# netzteil.net
KiCad netlist of a schematic drawn in EAGLE
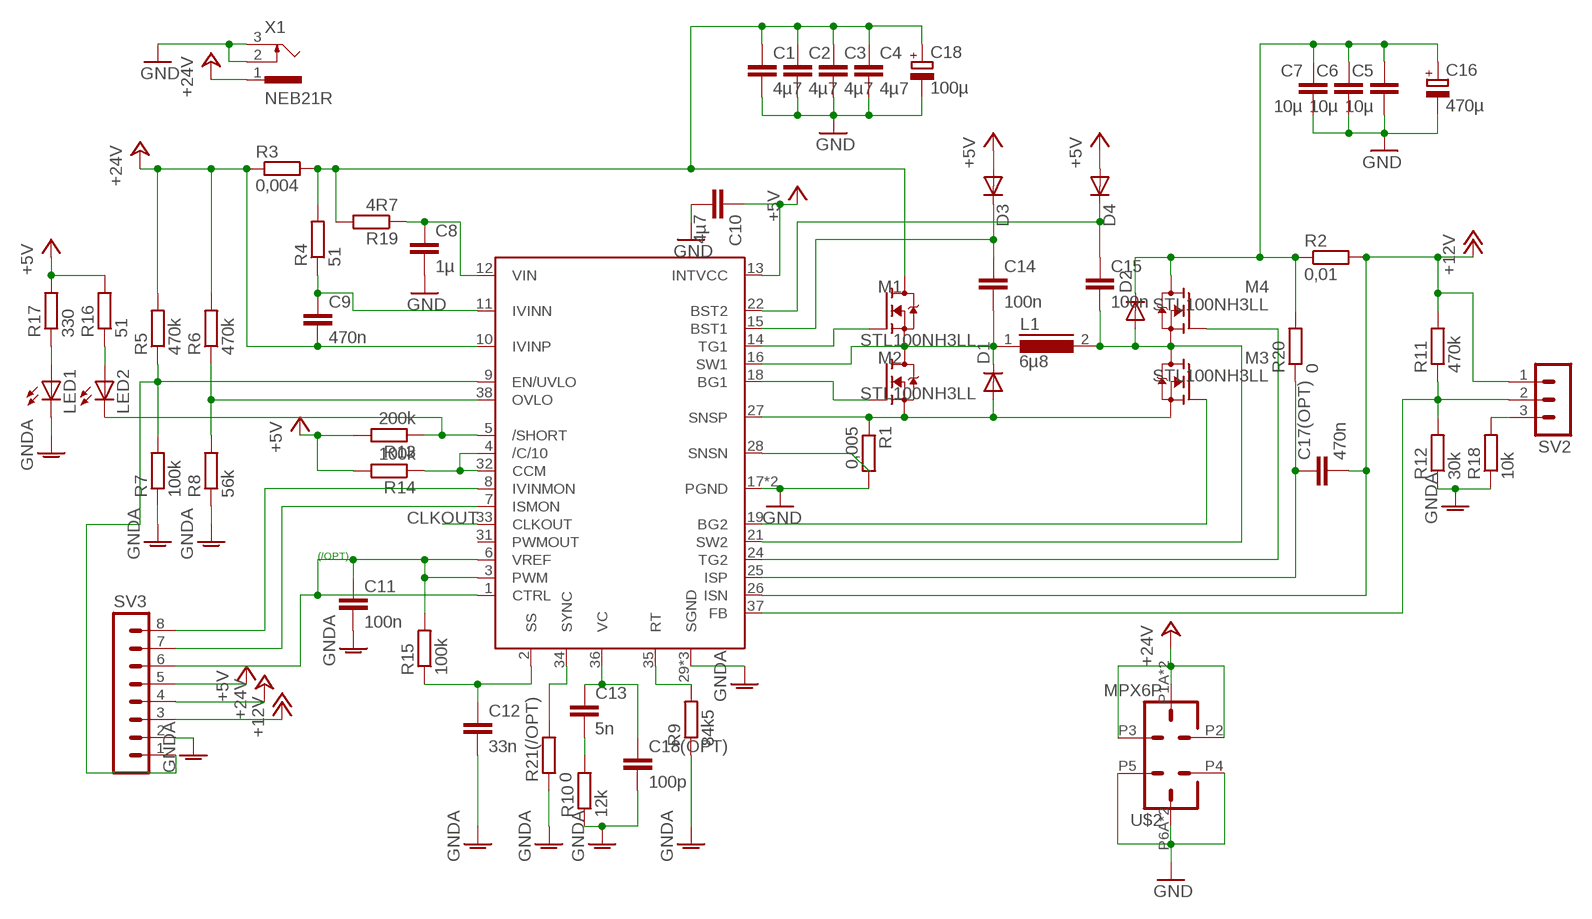
[diagram p0: schematic, sheet 1]

(export (version "E")
  (design (tool "Eeschema 10.0.6"))
  (components
    (comp (ref "C1")
      (value "4µ7")
      (footprint "eagle-import:C1206K")
      (libsource (lib "eagle-import") (part "C-EUC1206K"))
    )
    (comp (ref "C2")
      (value "4µ7")
      (footprint "eagle-import:C1206K")
      (libsource (lib "eagle-import") (part "C-EUC1206K"))
    )
    (comp (ref "C3")
      (value "4µ7")
      (footprint "eagle-import:C1206K")
      (libsource (lib "eagle-import") (part "C-EUC1206K"))
    )
    (comp (ref "C4")
      (value "4µ7")
      (footprint "eagle-import:C1206K")
      (libsource (lib "eagle-import") (part "C-EUC1206K"))
    )
    (comp (ref "C5")
      (value "10µ")
      (footprint "eagle-import:C1206K")
      (libsource (lib "eagle-import") (part "C-EUC1206K"))
    )
    (comp (ref "C6")
      (value "10µ")
      (footprint "eagle-import:C1206K")
      (libsource (lib "eagle-import") (part "C-EUC1206K"))
    )
    (comp (ref "C7")
      (value "10µ")
      (footprint "eagle-import:C1206K")
      (libsource (lib "eagle-import") (part "C-EUC1206K"))
    )
    (comp (ref "C8")
      (value "1µ")
      (footprint "eagle-import:C0805K")
      (libsource (lib "eagle-import") (part "C-EUC0805K"))
    )
    (comp (ref "C9")
      (value "470n")
      (footprint "eagle-import:C0805K")
      (libsource (lib "eagle-import") (part "C-EUC0805K"))
    )
    (comp (ref "C10")
      (value "4µ7")
      (footprint "eagle-import:C0805K")
      (libsource (lib "eagle-import") (part "C-EUC0805K"))
    )
    (comp (ref "C11")
      (value "100n")
      (footprint "eagle-import:C0805K")
      (libsource (lib "eagle-import") (part "C-EUC0805K"))
    )
    (comp (ref "C12")
      (value "33n")
      (footprint "eagle-import:C0805K")
      (libsource (lib "eagle-import") (part "C-EUC0805K"))
    )
    (comp (ref "C13")
      (value "5n")
      (footprint "eagle-import:C0805K")
      (libsource (lib "eagle-import") (part "C-EUC0805K"))
    )
    (comp (ref "C14")
      (value "100n")
      (footprint "eagle-import:C0805K")
      (libsource (lib "eagle-import") (part "C-EUC0805K"))
    )
    (comp (ref "C15")
      (value "100n")
      (footprint "eagle-import:C0805K")
      (libsource (lib "eagle-import") (part "C-EUC0805K"))
    )
    (comp (ref "C16")
      (value "470µ")
      (footprint "eagle-import:153CLV-1010")
      (libsource (lib "eagle-import") (part "CPOL-EU153CLV-1010"))
    )
    (comp (ref "C17(OPT)")
      (value "470n")
      (footprint "eagle-import:C0805K")
      (libsource (lib "eagle-import") (part "C-EUC0805K"))
    )
    (comp (ref "C18")
      (value "100µ")
      (footprint "eagle-import:153CLV-0605")
      (libsource (lib "eagle-import") (part "CPOL-EU153CLV-0605"))
    )
    (comp (ref "C18(OPT)")
      (value "100p")
      (footprint "eagle-import:C0805K")
      (libsource (lib "eagle-import") (part "C-EUC0805K"))
    )
    (comp (ref "D1")
      (value "DIODE-SOD323-R")
      (footprint "eagle-import:SOD323-R")
      (libsource (lib "eagle-import") (part "DIODE-SOD323-R"))
    )
    (comp (ref "D2")
      (value "DIODE-SOD323-R")
      (footprint "eagle-import:SOD323-R")
      (libsource (lib "eagle-import") (part "DIODE-SOD323-R"))
    )
    (comp (ref "D3")
      (value "DIODE-SOD323-R")
      (footprint "eagle-import:SOD323-R")
      (libsource (lib "eagle-import") (part "DIODE-SOD323-R"))
    )
    (comp (ref "D4")
      (value "DIODE-SOD323-R")
      (footprint "eagle-import:SOD323-R")
      (libsource (lib "eagle-import") (part "DIODE-SOD323-R"))
    )
    (comp (ref "L1")
      (value "6µ8")
      (footprint "eagle-import:DR125")
      (libsource (lib "eagle-import") (part "DR125"))
    )
    (comp (ref "LED1")
      (value "LEDSML0805")
      (footprint "eagle-import:SML0805")
      (libsource (lib "eagle-import") (part "LEDSML0805"))
    )
    (comp (ref "LED2")
      (value "LEDSML0805")
      (footprint "eagle-import:SML0805")
      (libsource (lib "eagle-import") (part "LEDSML0805"))
    )
    (comp (ref "M1")
      (value "STL100NH3LL")
      (footprint "eagle-import:PG-TDSON-8")
      (libsource (lib "eagle-import") (part "STL100NH3LL"))
    )
    (comp (ref "M2")
      (value "STL100NH3LL")
      (footprint "eagle-import:PG-TDSON-8")
      (libsource (lib "eagle-import") (part "STL100NH3LL"))
    )
    (comp (ref "M3")
      (value "STL100NH3LL")
      (footprint "eagle-import:PG-TDSON-8")
      (libsource (lib "eagle-import") (part "STL100NH3LL"))
    )
    (comp (ref "M4")
      (value "STL100NH3LL")
      (footprint "eagle-import:PG-TDSON-8")
      (libsource (lib "eagle-import") (part "STL100NH3LL"))
    )
    (comp (ref "R1")
      (value "0,005")
      (footprint "eagle-import:R2512")
      (libsource (lib "eagle-import") (part "R-EU_R2512"))
    )
    (comp (ref "R2")
      (value "0,01")
      (footprint "eagle-import:R2512")
      (libsource (lib "eagle-import") (part "R-EU_R2512"))
    )
    (comp (ref "R3")
      (value "0,004")
      (footprint "eagle-import:R2512")
      (libsource (lib "eagle-import") (part "R-EU_R2512"))
    )
    (comp (ref "R4")
      (value "51")
      (footprint "eagle-import:M0805")
      (libsource (lib "eagle-import") (part "R-EU_M0805"))
    )
    (comp (ref "R5")
      (value "470k")
      (footprint "eagle-import:M0805")
      (libsource (lib "eagle-import") (part "R-EU_M0805"))
    )
    (comp (ref "R6")
      (value "470k")
      (footprint "eagle-import:M0805")
      (libsource (lib "eagle-import") (part "R-EU_M0805"))
    )
    (comp (ref "R7")
      (value "100k")
      (footprint "eagle-import:M0805")
      (libsource (lib "eagle-import") (part "R-EU_M0805"))
    )
    (comp (ref "R8")
      (value "56k")
      (footprint "eagle-import:M0805")
      (libsource (lib "eagle-import") (part "R-EU_M0805"))
    )
    (comp (ref "R9")
      (value "84k5")
      (footprint "eagle-import:M0805")
      (libsource (lib "eagle-import") (part "R-EU_M0805"))
    )
    (comp (ref "R10")
      (value "12k")
      (footprint "eagle-import:M0805")
      (libsource (lib "eagle-import") (part "R-EU_M0805"))
    )
    (comp (ref "R11")
      (value "470k")
      (footprint "eagle-import:M0805")
      (libsource (lib "eagle-import") (part "R-EU_M0805"))
    )
    (comp (ref "R12")
      (value "30k")
      (footprint "eagle-import:M0805")
      (libsource (lib "eagle-import") (part "R-EU_M0805"))
    )
    (comp (ref "R13")
      (value "200k")
      (footprint "eagle-import:M0805")
      (libsource (lib "eagle-import") (part "R-EU_M0805"))
    )
    (comp (ref "R14")
      (value "100k")
      (footprint "eagle-import:M0805")
      (libsource (lib "eagle-import") (part "R-EU_M0805"))
    )
    (comp (ref "R15")
      (value "100k")
      (footprint "eagle-import:M0805")
      (libsource (lib "eagle-import") (part "R-EU_M0805"))
    )
    (comp (ref "R16")
      (value "51")
      (footprint "eagle-import:M0805")
      (libsource (lib "eagle-import") (part "R-EU_M0805"))
    )
    (comp (ref "R17")
      (value "330")
      (footprint "eagle-import:M0805")
      (libsource (lib "eagle-import") (part "R-EU_M0805"))
    )
    (comp (ref "R18")
      (value "10k")
      (footprint "eagle-import:M0805")
      (libsource (lib "eagle-import") (part "R-EU_M0805"))
    )
    (comp (ref "R19")
      (value "4R7")
      (footprint "eagle-import:M0805")
      (libsource (lib "eagle-import") (part "R-EU_M0805"))
    )
    (comp (ref "R20")
      (value "0")
      (footprint "eagle-import:M0805")
      (libsource (lib "eagle-import") (part "R-EU_M0805"))
    )
    (comp (ref "R21(/OPT)")
      (value "0")
      (footprint "eagle-import:M0805")
      (libsource (lib "eagle-import") (part "R-EU_M0805"))
    )
    (comp (ref "SV2")
      (value "MA03-1")
      (footprint "eagle-import:MA03-1")
      (libsource (lib "eagle-import") (part "MA03-1"))
    )
    (comp (ref "SV3")
      (value "MA08-1")
      (footprint "eagle-import:MA08-1")
      (libsource (lib "eagle-import") (part "MA08-1"))
    )
    (comp (ref "U$1")
      (value "LT3790")
      (footprint "eagle-import:HTSSOP38DCP")
      (libsource (lib "eagle-import") (part "LT3790"))
    )
    (comp (ref "U$2")
      (value "MPX6P")
      (footprint "eagle-import:MPX6")
      (libsource (lib "eagle-import") (part "MPX6P"))
    )
    (comp (ref "X1")
      (value "NEB21R")
      (footprint "eagle-import:NEB21R")
      (fields (field (name "MPN") "NEB 21 R"))
      (libsource (lib "eagle-import") (part "NEB21R"))
    )
  )
  (nets
    (net (code "1") (name "+5V") (class "Default")
      (node (ref "C10") (pin "1") (pinfunction "1_1") (pintype "passive"))
      (node (ref "D3") (pin "A") (pinfunction "A_A") (pintype "passive"))
      (node (ref "D4") (pin "A") (pinfunction "A_A") (pintype "passive"))
      (node (ref "R13") (pin "2") (pinfunction "2_2") (pintype "passive"))
      (node (ref "R14") (pin "2") (pinfunction "2_2") (pintype "passive"))
      (node (ref "R16") (pin "2") (pinfunction "2_2") (pintype "passive"))
      (node (ref "R17") (pin "2") (pinfunction "2_2") (pintype "passive"))
      (node (ref "SV3") (pin "5") (pinfunction "5_5") (pintype "passive"))
      (node (ref "U$1") (pin "13") (pinfunction "INTVCC_13") (pintype "bidirectional"))
    )
    (net (code "2") (name "+12V") (class "Default")
      (node (ref "C17(OPT)") (pin "2") (pinfunction "2_2") (pintype "passive"))
      (node (ref "R11") (pin "2") (pinfunction "2_2") (pintype "passive"))
      (node (ref "R2") (pin "2") (pinfunction "2_2") (pintype "passive"))
      (node (ref "SV2") (pin "1") (pinfunction "1_1") (pintype "passive"))
      (node (ref "SV3") (pin "3") (pinfunction "3_3") (pintype "passive"))
      (node (ref "U$1") (pin "26") (pinfunction "ISN_26") (pintype "bidirectional"))
    )
    (net (code "3") (name "+24V") (class "Default")
      (node (ref "C9") (pin "2") (pinfunction "2_2") (pintype "passive"))
      (node (ref "R3") (pin "1") (pinfunction "1_1") (pintype "passive"))
      (node (ref "R5") (pin "2") (pinfunction "2_2") (pintype "passive"))
      (node (ref "R6") (pin "2") (pinfunction "2_2") (pintype "passive"))
      (node (ref "SV3") (pin "4") (pinfunction "4_4") (pintype "passive"))
      (node (ref "U$1") (pin "10") (pinfunction "IVINP_10") (pintype "bidirectional"))
      (node (ref "U$2") (pin "P1A") (pinfunction "1_P1A") (pintype "power_in"))
      (node (ref "U$2") (pin "P1B") (pinfunction "1_P1B") (pintype "power_in"))
      (node (ref "U$2") (pin "P2") (pinfunction "2_P2") (pintype "power_in"))
      (node (ref "U$2") (pin "P3") (pinfunction "3_P3") (pintype "power_in"))
      (node (ref "X1") (pin "1") (pinfunction "1_1") (pintype "passive"))
    )
    (net (code "4") (name "/CLKOUT") (class "Default")
      (node (ref "U$1") (pin "33") (pinfunction "CLKOUT_33") (pintype "bidirectional"))
    )
    (net (code "5") (name "GND") (class "Default")
      (node (ref "C1") (pin "2") (pinfunction "2_2") (pintype "passive"))
      (node (ref "C10") (pin "2") (pinfunction "2_2") (pintype "passive"))
      (node (ref "C16") (pin "-") (pinfunction "-_-") (pintype "passive"))
      (node (ref "C18") (pin "-") (pinfunction "-_-") (pintype "passive"))
      (node (ref "C2") (pin "2") (pinfunction "2_2") (pintype "passive"))
      (node (ref "C3") (pin "2") (pinfunction "2_2") (pintype "passive"))
      (node (ref "C4") (pin "2") (pinfunction "2_2") (pintype "passive"))
      (node (ref "C5") (pin "2") (pinfunction "2_2") (pintype "passive"))
      (node (ref "C6") (pin "2") (pinfunction "2_2") (pintype "passive"))
      (node (ref "C7") (pin "2") (pinfunction "2_2") (pintype "passive"))
      (node (ref "C8") (pin "2") (pinfunction "2_2") (pintype "passive"))
      (node (ref "R1") (pin "2") (pinfunction "2_2") (pintype "passive"))
      (node (ref "U$1") (pin "17") (pinfunction "PGND_17") (pintype "bidirectional"))
      (node (ref "U$1") (pin "20") (pinfunction "PGND_20") (pintype "bidirectional"))
      (node (ref "U$2") (pin "P4") (pinfunction "4_P4") (pintype "power_in"))
      (node (ref "U$2") (pin "P5") (pinfunction "5_P5") (pintype "power_in"))
      (node (ref "U$2") (pin "P6A") (pinfunction "6_P6A") (pintype "power_in"))
      (node (ref "U$2") (pin "P6B") (pinfunction "6_P6B") (pintype "power_in"))
      (node (ref "X1") (pin "2") (pinfunction "2_2") (pintype "passive"))
      (node (ref "X1") (pin "3") (pinfunction "3_3") (pintype "passive"))
    )
    (net (code "6") (name "GNDA") (class "Default")
      (node (ref "C11") (pin "2") (pinfunction "2_2") (pintype "passive"))
      (node (ref "C12") (pin "2") (pinfunction "2_2") (pintype "passive"))
      (node (ref "C18(OPT)") (pin "2") (pinfunction "2_2") (pintype "passive"))
      (node (ref "LED1") (pin "C") (pinfunction "C_C") (pintype "passive"))
      (node (ref "R10") (pin "1") (pinfunction "1_1") (pintype "passive"))
      (node (ref "R12") (pin "1") (pinfunction "1_1") (pintype "passive"))
      (node (ref "R18") (pin "1") (pinfunction "1_1") (pintype "passive"))
      (node (ref "R21(/OPT)") (pin "1") (pinfunction "1_1") (pintype "passive"))
      (node (ref "R7") (pin "1") (pinfunction "1_1") (pintype "passive"))
      (node (ref "R8") (pin "1") (pinfunction "1_1") (pintype "passive"))
      (node (ref "R9") (pin "1") (pinfunction "1_1") (pintype "passive"))
      (node (ref "SV3") (pin "2") (pinfunction "2_2") (pintype "passive"))
      (node (ref "U$1") (pin "29") (pinfunction "SGND_29") (pintype "bidirectional"))
      (node (ref "U$1") (pin "30") (pinfunction "SGND_30") (pintype "bidirectional"))
      (node (ref "U$1") (pin "EXP@1") (pinfunction "SGND_EXP@1") (pintype "bidirectional"))
    )
    (net (code "7") (name "Net-(C1-Pad1)") (class "Default")
      (node (ref "C1") (pin "1") (pinfunction "1_1") (pintype "passive"))
      (node (ref "C18") (pin "+") (pinfunction "+_+") (pintype "passive"))
      (node (ref "C2") (pin "1") (pinfunction "1_1") (pintype "passive"))
      (node (ref "C3") (pin "1") (pinfunction "1_1") (pintype "passive"))
      (node (ref "C4") (pin "1") (pinfunction "1_1") (pintype "passive"))
      (node (ref "M1") (pin "5") (pinfunction "D_5") (pintype "passive"))
      (node (ref "M1") (pin "6") (pinfunction "D_6") (pintype "passive"))
      (node (ref "M1") (pin "7") (pinfunction "D_7") (pintype "passive"))
      (node (ref "M1") (pin "8") (pinfunction "D_8") (pintype "passive"))
      (node (ref "M1") (pin "TH") (pinfunction "D_TH") (pintype "passive"))
      (node (ref "R19") (pin "2") (pinfunction "2_2") (pintype "passive"))
      (node (ref "R3") (pin "2") (pinfunction "2_2") (pintype "passive"))
      (node (ref "R4") (pin "2") (pinfunction "2_2") (pintype "passive"))
    )
    (net (code "8") (name "Net-(C13-Pad2)") (class "Default")
      (node (ref "C13") (pin "2") (pinfunction "2_2") (pintype "passive"))
      (node (ref "R10") (pin "2") (pinfunction "2_2") (pintype "passive"))
    )
    (net (code "9") (name "Net-(C16-Pad+)") (class "Default")
      (node (ref "C16") (pin "+") (pinfunction "+_+") (pintype "passive"))
      (node (ref "C5") (pin "1") (pinfunction "1_1") (pintype "passive"))
      (node (ref "C6") (pin "1") (pinfunction "1_1") (pintype "passive"))
      (node (ref "C7") (pin "1") (pinfunction "1_1") (pintype "passive"))
      (node (ref "D2") (pin "C") (pinfunction "C_C") (pintype "passive"))
      (node (ref "M4") (pin "5") (pinfunction "D_5") (pintype "passive"))
      (node (ref "M4") (pin "6") (pinfunction "D_6") (pintype "passive"))
      (node (ref "M4") (pin "7") (pinfunction "D_7") (pintype "passive"))
      (node (ref "M4") (pin "8") (pinfunction "D_8") (pintype "passive"))
      (node (ref "M4") (pin "TH") (pinfunction "D_TH") (pintype "passive"))
      (node (ref "R2") (pin "1") (pinfunction "1_1") (pintype "passive"))
      (node (ref "R20") (pin "2") (pinfunction "2_2") (pintype "passive"))
    )
    (net (code "10") (name "Net-(LED1-PadA)") (class "Default")
      (node (ref "LED1") (pin "A") (pinfunction "A_A") (pintype "passive"))
      (node (ref "R17") (pin "1") (pinfunction "1_1") (pintype "passive"))
    )
    (net (code "11") (name "Net-(LED2-PadA)") (class "Default")
      (node (ref "LED2") (pin "A") (pinfunction "A_A") (pintype "passive"))
      (node (ref "R16") (pin "1") (pinfunction "1_1") (pintype "passive"))
    )
    (net (code "12") (name "Net-(M1-G)") (class "Default")
      (node (ref "M1") (pin "4") (pinfunction "G_4") (pintype "passive"))
      (node (ref "U$1") (pin "14") (pinfunction "TG1_14") (pintype "bidirectional"))
    )
    (net (code "13") (name "Net-(M2-G)") (class "Default")
      (node (ref "M2") (pin "4") (pinfunction "G_4") (pintype "passive"))
      (node (ref "U$1") (pin "18") (pinfunction "BG1_18") (pintype "bidirectional"))
    )
    (net (code "14") (name "Net-(M3-G)") (class "Default")
      (node (ref "M3") (pin "4") (pinfunction "G_4") (pintype "passive"))
      (node (ref "U$1") (pin "19") (pinfunction "BG2_19") (pintype "bidirectional"))
    )
    (net (code "15") (name "Net-(M4-G)") (class "Default")
      (node (ref "M4") (pin "4") (pinfunction "G_4") (pintype "passive"))
      (node (ref "U$1") (pin "24") (pinfunction "TG2_24") (pintype "bidirectional"))
    )
    (net (code "16") (name "Net-(R18-Pad2)") (class "Default")
      (node (ref "R18") (pin "2") (pinfunction "2_2") (pintype "passive"))
      (node (ref "SV2") (pin "3") (pinfunction "3_3") (pintype "passive"))
    )
    (net (code "17") (name "Net-(U$1-BST1)") (class "Default")
      (node (ref "C14") (pin "1") (pinfunction "1_1") (pintype "passive"))
      (node (ref "D3") (pin "C") (pinfunction "C_C") (pintype "passive"))
      (node (ref "U$1") (pin "15") (pinfunction "BST1_15") (pintype "bidirectional"))
    )
    (net (code "18") (name "Net-(U$1-BST2)") (class "Default")
      (node (ref "C15") (pin "1") (pinfunction "1_1") (pintype "passive"))
      (node (ref "D4") (pin "C") (pinfunction "C_C") (pintype "passive"))
      (node (ref "U$1") (pin "22") (pinfunction "BST2_22") (pintype "bidirectional"))
    )
    (net (code "19") (name "Net-(U$1-CCM)") (class "Default")
      (node (ref "R14") (pin "1") (pinfunction "1_1") (pintype "passive"))
      (node (ref "U$1") (pin "32") (pinfunction "CCM_32") (pintype "bidirectional"))
      (node (ref "U$1") (pin "4") (pinfunction "/C/10_4") (pintype "bidirectional"))
    )
    (net (code "20") (name "Net-(U$1-CTRL)") (class "Default")
      (node (ref "C11") (pin "1") (pinfunction "1_1") (pintype "passive"))
      (node (ref "R15") (pin "2") (pinfunction "2_2") (pintype "passive"))
      (node (ref "SV3") (pin "6") (pinfunction "6_6") (pintype "passive"))
      (node (ref "U$1") (pin "1") (pinfunction "CTRL_1") (pintype "bidirectional"))
      (node (ref "U$1") (pin "3") (pinfunction "PWM_3") (pintype "bidirectional"))
      (node (ref "U$1") (pin "6") (pinfunction "VREF_6") (pintype "bidirectional"))
    )
    (net (code "21") (name "Net-(U$1-EN{slash}UVLO)") (class "Default")
      (node (ref "R5") (pin "1") (pinfunction "1_1") (pintype "passive"))
      (node (ref "R7") (pin "2") (pinfunction "2_2") (pintype "passive"))
      (node (ref "SV3") (pin "1") (pinfunction "1_1") (pintype "passive"))
      (node (ref "U$1") (pin "9") (pinfunction "EN/UVLO_9") (pintype "bidirectional"))
    )
    (net (code "22") (name "Net-(U$1-FB)") (class "Default")
      (node (ref "R11") (pin "1") (pinfunction "1_1") (pintype "passive"))
      (node (ref "R12") (pin "2") (pinfunction "2_2") (pintype "passive"))
      (node (ref "SV2") (pin "2") (pinfunction "2_2") (pintype "passive"))
      (node (ref "U$1") (pin "37") (pinfunction "FB_37") (pintype "bidirectional"))
    )
    (net (code "23") (name "Net-(U$1-ISMON)") (class "Default")
      (node (ref "SV3") (pin "7") (pinfunction "7_7") (pintype "passive"))
      (node (ref "U$1") (pin "7") (pinfunction "ISMON_7") (pintype "bidirectional"))
    )
    (net (code "24") (name "Net-(U$1-ISP)") (class "Default")
      (node (ref "C17(OPT)") (pin "1") (pinfunction "1_1") (pintype "passive"))
      (node (ref "R20") (pin "1") (pinfunction "1_1") (pintype "passive"))
      (node (ref "U$1") (pin "25") (pinfunction "ISP_25") (pintype "bidirectional"))
    )
    (net (code "25") (name "Net-(U$1-IVINMON)") (class "Default")
      (node (ref "SV3") (pin "8") (pinfunction "8_8") (pintype "passive"))
      (node (ref "U$1") (pin "8") (pinfunction "IVINMON_8") (pintype "bidirectional"))
    )
    (net (code "26") (name "Net-(U$1-IVINN)") (class "Default")
      (node (ref "C9") (pin "1") (pinfunction "1_1") (pintype "passive"))
      (node (ref "R4") (pin "1") (pinfunction "1_1") (pintype "passive"))
      (node (ref "U$1") (pin "11") (pinfunction "IVINN_11") (pintype "bidirectional"))
    )
    (net (code "27") (name "Net-(U$1-OVLO)") (class "Default")
      (node (ref "R6") (pin "1") (pinfunction "1_1") (pintype "passive"))
      (node (ref "R8") (pin "2") (pinfunction "2_2") (pintype "passive"))
      (node (ref "U$1") (pin "38") (pinfunction "OVLO_38") (pintype "bidirectional"))
    )
    (net (code "28") (name "Net-(U$1-RT)") (class "Default")
      (node (ref "R9") (pin "2") (pinfunction "2_2") (pintype "passive"))
      (node (ref "U$1") (pin "35") (pinfunction "RT_35") (pintype "bidirectional"))
    )
    (net (code "29") (name "Net-(U$1-SNSP)") (class "Default")
      (node (ref "D1") (pin "A") (pinfunction "A_A") (pintype "passive"))
      (node (ref "M2") (pin "1") (pinfunction "S_1") (pintype "passive"))
      (node (ref "M2") (pin "2") (pinfunction "S_2") (pintype "passive"))
      (node (ref "M2") (pin "3") (pinfunction "S_3") (pintype "passive"))
      (node (ref "M3") (pin "1") (pinfunction "S_1") (pintype "passive"))
      (node (ref "M3") (pin "2") (pinfunction "S_2") (pintype "passive"))
      (node (ref "M3") (pin "3") (pinfunction "S_3") (pintype "passive"))
      (node (ref "R1") (pin "1") (pinfunction "1_1") (pintype "passive"))
      (node (ref "U$1") (pin "27") (pinfunction "SNSP_27") (pintype "bidirectional"))
    )
    (net (code "30") (name "Net-(U$1-SS)") (class "Default")
      (node (ref "C12") (pin "1") (pinfunction "1_1") (pintype "passive"))
      (node (ref "R15") (pin "1") (pinfunction "1_1") (pintype "passive"))
      (node (ref "U$1") (pin "2") (pinfunction "SS_2") (pintype "bidirectional"))
    )
    (net (code "31") (name "Net-(U$1-SW1)") (class "Default")
      (node (ref "C14") (pin "2") (pinfunction "2_2") (pintype "passive"))
      (node (ref "D1") (pin "C") (pinfunction "C_C") (pintype "passive"))
      (node (ref "L1") (pin "1") (pinfunction "1_1") (pintype "passive"))
      (node (ref "M1") (pin "1") (pinfunction "S_1") (pintype "passive"))
      (node (ref "M1") (pin "2") (pinfunction "S_2") (pintype "passive"))
      (node (ref "M1") (pin "3") (pinfunction "S_3") (pintype "passive"))
      (node (ref "M2") (pin "5") (pinfunction "D_5") (pintype "passive"))
      (node (ref "M2") (pin "6") (pinfunction "D_6") (pintype "passive"))
      (node (ref "M2") (pin "7") (pinfunction "D_7") (pintype "passive"))
      (node (ref "M2") (pin "8") (pinfunction "D_8") (pintype "passive"))
      (node (ref "M2") (pin "TH") (pinfunction "D_TH") (pintype "passive"))
      (node (ref "U$1") (pin "16") (pinfunction "SW1_16") (pintype "bidirectional"))
    )
    (net (code "32") (name "Net-(U$1-SW2)") (class "Default")
      (node (ref "C15") (pin "2") (pinfunction "2_2") (pintype "passive"))
      (node (ref "D2") (pin "A") (pinfunction "A_A") (pintype "passive"))
      (node (ref "L1") (pin "2") (pinfunction "2_2") (pintype "passive"))
      (node (ref "M3") (pin "5") (pinfunction "D_5") (pintype "passive"))
      (node (ref "M3") (pin "6") (pinfunction "D_6") (pintype "passive"))
      (node (ref "M3") (pin "7") (pinfunction "D_7") (pintype "passive"))
      (node (ref "M3") (pin "8") (pinfunction "D_8") (pintype "passive"))
      (node (ref "M3") (pin "TH") (pinfunction "D_TH") (pintype "passive"))
      (node (ref "M4") (pin "1") (pinfunction "S_1") (pintype "passive"))
      (node (ref "M4") (pin "2") (pinfunction "S_2") (pintype "passive"))
      (node (ref "M4") (pin "3") (pinfunction "S_3") (pintype "passive"))
      (node (ref "U$1") (pin "21") (pinfunction "SW2_21") (pintype "bidirectional"))
    )
    (net (code "33") (name "Net-(U$1-SYNC)") (class "Default")
      (node (ref "R21(/OPT)") (pin "2") (pinfunction "2_2") (pintype "passive"))
      (node (ref "U$1") (pin "34") (pinfunction "SYNC_34") (pintype "bidirectional"))
    )
    (net (code "34") (name "Net-(U$1-VC)") (class "Default")
      (node (ref "C13") (pin "1") (pinfunction "1_1") (pintype "passive"))
      (node (ref "C18(OPT)") (pin "1") (pinfunction "1_1") (pintype "passive"))
      (node (ref "U$1") (pin "36") (pinfunction "VC_36") (pintype "bidirectional"))
    )
    (net (code "35") (name "Net-(U$1-VIN)") (class "Default")
      (node (ref "C8") (pin "1") (pinfunction "1_1") (pintype "passive"))
      (node (ref "R19") (pin "1") (pinfunction "1_1") (pintype "passive"))
      (node (ref "U$1") (pin "12") (pinfunction "VIN_12") (pintype "bidirectional"))
    )
    (net (code "36") (name "Net-(U$1-{slash}SHORT)") (class "Default")
      (node (ref "LED2") (pin "C") (pinfunction "C_C") (pintype "passive"))
      (node (ref "R13") (pin "1") (pinfunction "1_1") (pintype "passive"))
      (node (ref "U$1") (pin "5") (pinfunction "/SHORT_5") (pintype "bidirectional"))
    )
    (net (code "37") (name "unconnected-(U$1-PWMOUT-Pad31)") (class "Default")
      (node (ref "U$1") (pin "31") (pinfunction "PWMOUT_31") (pintype "bidirectional"))
    )
    (net (code "38") (name "unconnected-(U$1-SNSN-Pad28)") (class "Default")
      (node (ref "U$1") (pin "28") (pinfunction "SNSN_28") (pintype "bidirectional"))
    )
  )
)
